# esp8266-temp.net
KiCad netlist of a schematic drawn in EAGLE
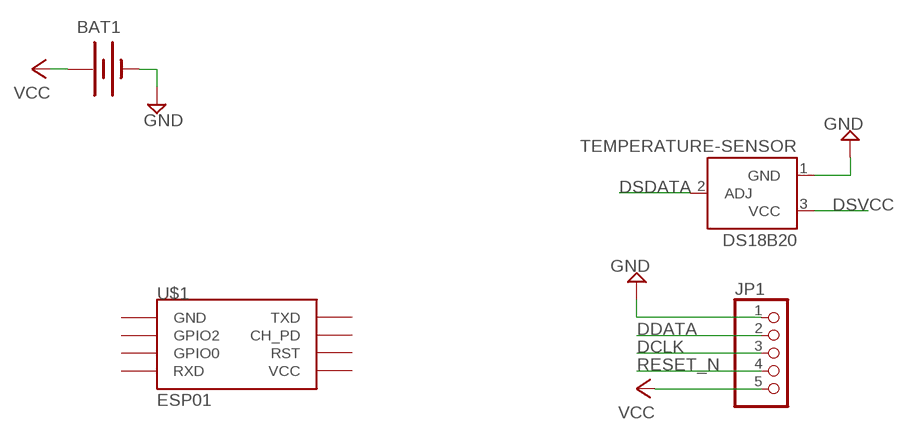
[diagram p0: schematic, sheet 1]

(export (version "E")
  (design (tool "Eeschema 10.0.6"))
  (components
    (comp (ref "BAT1")
      (value "BATTERY20PTH")
      (footprint "eagle-import:BATTCOM_20MM_PTH")
      (libsource (lib "eagle-import") (part "BATTERY20PTH"))
    )
    (comp (ref "DS18B20")
      (value "TEMPERATURE-SENSOR")
      (footprint "eagle-import:TO-92")
      (libsource (lib "eagle-import") (part "TEMPERATURE-SENSOR"))
    )
    (comp (ref "JP1")
      (value "PINHD-1X5")
      (footprint "eagle-import:1X05")
      (libsource (lib "eagle-import") (part "PINHD-1X5"))
    )
    (comp (ref "U$1")
      (value "ESP01")
      (footprint "eagle-import:ESP01")
      (libsource (lib "eagle-import") (part "ESP01"))
    )
  )
  (nets
    (net (code "1") (name "/DCLK") (class "Default")
      (node (ref "JP1") (pin "3") (pinfunction "3_3") (pintype "passive"))
    )
    (net (code "2") (name "/DDATA") (class "Default")
      (node (ref "JP1") (pin "2") (pinfunction "2_2") (pintype "passive"))
    )
    (net (code "3") (name "/DSDATA") (class "Default")
      (node (ref "DS18B20") (pin "2") (pinfunction "ADJ_2") (pintype "bidirectional"))
    )
    (net (code "4") (name "/DSVCC") (class "Default")
      (node (ref "DS18B20") (pin "3") (pinfunction "VCC_3") (pintype "bidirectional"))
    )
    (net (code "5") (name "/RESET_N") (class "Default")
      (node (ref "JP1") (pin "4") (pinfunction "4_4") (pintype "passive"))
    )
    (net (code "6") (name "GND") (class "Default")
      (node (ref "BAT1") (pin "2") (pinfunction "-_2") (pintype "power_in"))
      (node (ref "DS18B20") (pin "1") (pinfunction "GND_1") (pintype "bidirectional"))
      (node (ref "JP1") (pin "1") (pinfunction "1_1") (pintype "passive"))
    )
    (net (code "7") (name "VCC") (class "Default")
      (node (ref "BAT1") (pin "1") (pinfunction "+_1") (pintype "power_in"))
      (node (ref "JP1") (pin "5") (pinfunction "5_5") (pintype "passive"))
    )
    (net (code "8") (name "unconnected-(U$1-PadCH_PD)") (class "Default")
      (node (ref "U$1") (pin "CH_PD") (pinfunction "CH_PD_CH_PD") (pintype "bidirectional"))
    )
    (net (code "9") (name "unconnected-(U$1-PadGND)") (class "Default")
      (node (ref "U$1") (pin "GND") (pinfunction "GND_GND") (pintype "bidirectional"))
    )
    (net (code "10") (name "unconnected-(U$1-PadGPIO0)") (class "Default")
      (node (ref "U$1") (pin "GPIO0") (pinfunction "GPIO0_GPIO0") (pintype "bidirectional"))
    )
    (net (code "11") (name "unconnected-(U$1-PadGPIO2)") (class "Default")
      (node (ref "U$1") (pin "GPIO2") (pinfunction "GPIO2_GPIO2") (pintype "bidirectional"))
    )
    (net (code "12") (name "unconnected-(U$1-PadRST)") (class "Default")
      (node (ref "U$1") (pin "RST") (pinfunction "RST_RST") (pintype "bidirectional"))
    )
    (net (code "13") (name "unconnected-(U$1-PadVCC)") (class "Default")
      (node (ref "U$1") (pin "VCC") (pinfunction "VCC_VCC") (pintype "bidirectional"))
    )
    (net (code "14") (name "unconnected-(U$1-RXD-PadRX)") (class "Default")
      (node (ref "U$1") (pin "RX") (pinfunction "RXD_RX") (pintype "bidirectional"))
    )
    (net (code "15") (name "unconnected-(U$1-TXD-PadTX)") (class "Default")
      (node (ref "U$1") (pin "TX") (pinfunction "TXD_TX") (pintype "bidirectional"))
    )
  )
)
